# wifi.net
KiCad netlist of a schematic drawn in Altium Designer
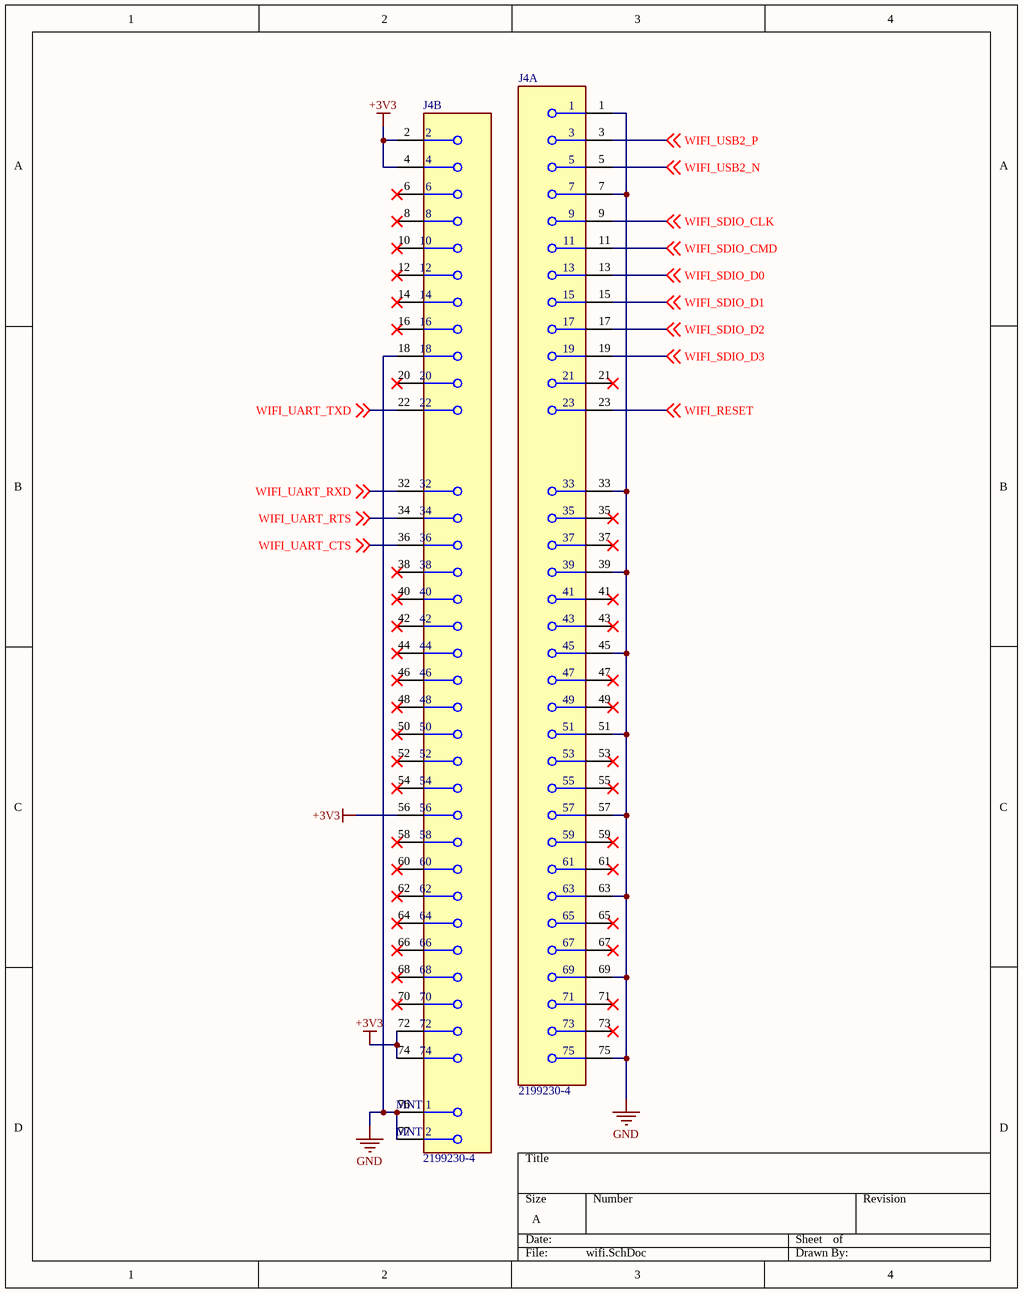
[diagram p0: wifi.SchDoc]

(export (version "E")
  (design (tool "Eeschema 10.0.6"))
  (components
    (comp (ref "J4")
      (value "2199230-4")
      (footprint "FP-2199230-4-MFG")
      (description "CONN FEMALE 67POS 0.020 GOLD")
      (fields
        (field (name "MANUFACTURER") "TE Connectivity")
        (field (name "OCTOPART") "https://octopart.com/2199230-4-te+connectivity-46436156")
      )
      (libsource (lib "Altium Content Vault") (part "6b4bc9aaecd91677fa565b830470f16"))
    )
  )
  (nets
    (net (code "1") (name "+3V3") (class "Default")
      (node (ref "J4") (pin "2") (pinfunction "2_2") (pintype "passive"))
      (node (ref "J4") (pin "4") (pinfunction "4_4") (pintype "passive"))
      (node (ref "J4") (pin "56") (pinfunction "56_56") (pintype "passive"))
      (node (ref "J4") (pin "72") (pinfunction "72_72") (pintype "passive"))
      (node (ref "J4") (pin "74") (pinfunction "74_74") (pintype "passive"))
    )
    (net (code "2") (name "GND") (class "Default")
      (node (ref "J4") (pin "1") (pinfunction "1_1") (pintype "passive"))
      (node (ref "J4") (pin "18") (pinfunction "18_18") (pintype "passive"))
      (node (ref "J4") (pin "33") (pinfunction "33_33") (pintype "passive"))
      (node (ref "J4") (pin "39") (pinfunction "39_39") (pintype "passive"))
      (node (ref "J4") (pin "45") (pinfunction "45_45") (pintype "passive"))
      (node (ref "J4") (pin "51") (pinfunction "51_51") (pintype "passive"))
      (node (ref "J4") (pin "57") (pinfunction "57_57") (pintype "passive"))
      (node (ref "J4") (pin "63") (pinfunction "63_63") (pintype "passive"))
      (node (ref "J4") (pin "69") (pinfunction "69_69") (pintype "passive"))
      (node (ref "J4") (pin "7") (pinfunction "7_7") (pintype "passive"))
      (node (ref "J4") (pin "75") (pinfunction "75_75") (pintype "passive"))
      (node (ref "J4") (pin "76") (pinfunction "MNT_1_76") (pintype "passive"))
      (node (ref "J4") (pin "77") (pinfunction "MNT_2_77") (pintype "passive"))
    )
    (net (code "3") (name "WIFI_RESET") (class "Default")
      (node (ref "J4") (pin "23") (pinfunction "23_23") (pintype "passive"))
    )
    (net (code "4") (name "WIFI_SDIO_CLK") (class "Default")
      (node (ref "J4") (pin "9") (pinfunction "9_9") (pintype "passive"))
    )
    (net (code "5") (name "WIFI_SDIO_CMD") (class "Default")
      (node (ref "J4") (pin "11") (pinfunction "11_11") (pintype "passive"))
    )
    (net (code "6") (name "WIFI_SDIO_D0") (class "Default")
      (node (ref "J4") (pin "13") (pinfunction "13_13") (pintype "passive"))
    )
    (net (code "7") (name "WIFI_SDIO_D1") (class "Default")
      (node (ref "J4") (pin "15") (pinfunction "15_15") (pintype "passive"))
    )
    (net (code "8") (name "WIFI_SDIO_D2") (class "Default")
      (node (ref "J4") (pin "17") (pinfunction "17_17") (pintype "passive"))
    )
    (net (code "9") (name "WIFI_SDIO_D3") (class "Default")
      (node (ref "J4") (pin "19") (pinfunction "19_19") (pintype "passive"))
    )
    (net (code "10") (name "WIFI_UART_CTS") (class "Default")
      (node (ref "J4") (pin "36") (pinfunction "36_36") (pintype "passive"))
    )
    (net (code "11") (name "WIFI_UART_RTS") (class "Default")
      (node (ref "J4") (pin "34") (pinfunction "34_34") (pintype "passive"))
    )
    (net (code "12") (name "WIFI_UART_RXD") (class "Default")
      (node (ref "J4") (pin "32") (pinfunction "32_32") (pintype "passive"))
    )
    (net (code "13") (name "WIFI_UART_TXD") (class "Default")
      (node (ref "J4") (pin "22") (pinfunction "22_22") (pintype "passive"))
    )
    (net (code "14") (name "WIFI_USB2_N") (class "Default")
      (node (ref "J4") (pin "5") (pinfunction "5_5") (pintype "passive"))
    )
    (net (code "15") (name "WIFI_USB2_P") (class "Default")
      (node (ref "J4") (pin "3") (pinfunction "3_3") (pintype "passive"))
    )
    (net (code "16") (name "unconnected-(J4-Pad6)") (class "Default")
      (node (ref "J4") (pin "6") (pinfunction "6_6") (pintype "passive+no_connect"))
    )
    (net (code "17") (name "unconnected-(J4-Pad8)") (class "Default")
      (node (ref "J4") (pin "8") (pinfunction "8_8") (pintype "passive+no_connect"))
    )
    (net (code "18") (name "unconnected-(J4-Pad10)") (class "Default")
      (node (ref "J4") (pin "10") (pinfunction "10_10") (pintype "passive+no_connect"))
    )
    (net (code "19") (name "unconnected-(J4-Pad12)") (class "Default")
      (node (ref "J4") (pin "12") (pinfunction "12_12") (pintype "passive+no_connect"))
    )
    (net (code "20") (name "unconnected-(J4-Pad14)") (class "Default")
      (node (ref "J4") (pin "14") (pinfunction "14_14") (pintype "passive+no_connect"))
    )
    (net (code "21") (name "unconnected-(J4-Pad16)") (class "Default")
      (node (ref "J4") (pin "16") (pinfunction "16_16") (pintype "passive+no_connect"))
    )
    (net (code "22") (name "unconnected-(J4-Pad20)") (class "Default")
      (node (ref "J4") (pin "20") (pinfunction "20_20") (pintype "passive+no_connect"))
    )
    (net (code "23") (name "unconnected-(J4-Pad21)") (class "Default")
      (node (ref "J4") (pin "21") (pinfunction "21_21") (pintype "passive+no_connect"))
    )
    (net (code "24") (name "unconnected-(J4-Pad35)") (class "Default")
      (node (ref "J4") (pin "35") (pinfunction "35_35") (pintype "passive+no_connect"))
    )
    (net (code "25") (name "unconnected-(J4-Pad37)") (class "Default")
      (node (ref "J4") (pin "37") (pinfunction "37_37") (pintype "passive+no_connect"))
    )
    (net (code "26") (name "unconnected-(J4-Pad38)") (class "Default")
      (node (ref "J4") (pin "38") (pinfunction "38_38") (pintype "passive+no_connect"))
    )
    (net (code "27") (name "unconnected-(J4-Pad40)") (class "Default")
      (node (ref "J4") (pin "40") (pinfunction "40_40") (pintype "passive+no_connect"))
    )
    (net (code "28") (name "unconnected-(J4-Pad41)") (class "Default")
      (node (ref "J4") (pin "41") (pinfunction "41_41") (pintype "passive+no_connect"))
    )
    (net (code "29") (name "unconnected-(J4-Pad42)") (class "Default")
      (node (ref "J4") (pin "42") (pinfunction "42_42") (pintype "passive+no_connect"))
    )
    (net (code "30") (name "unconnected-(J4-Pad43)") (class "Default")
      (node (ref "J4") (pin "43") (pinfunction "43_43") (pintype "passive+no_connect"))
    )
    (net (code "31") (name "unconnected-(J4-Pad44)") (class "Default")
      (node (ref "J4") (pin "44") (pinfunction "44_44") (pintype "passive+no_connect"))
    )
    (net (code "32") (name "unconnected-(J4-Pad46)") (class "Default")
      (node (ref "J4") (pin "46") (pinfunction "46_46") (pintype "passive+no_connect"))
    )
    (net (code "33") (name "unconnected-(J4-Pad47)") (class "Default")
      (node (ref "J4") (pin "47") (pinfunction "47_47") (pintype "passive+no_connect"))
    )
    (net (code "34") (name "unconnected-(J4-Pad48)") (class "Default")
      (node (ref "J4") (pin "48") (pinfunction "48_48") (pintype "passive+no_connect"))
    )
    (net (code "35") (name "unconnected-(J4-Pad49)") (class "Default")
      (node (ref "J4") (pin "49") (pinfunction "49_49") (pintype "passive+no_connect"))
    )
    (net (code "36") (name "unconnected-(J4-Pad50)") (class "Default")
      (node (ref "J4") (pin "50") (pinfunction "50_50") (pintype "passive+no_connect"))
    )
    (net (code "37") (name "unconnected-(J4-Pad52)") (class "Default")
      (node (ref "J4") (pin "52") (pinfunction "52_52") (pintype "passive+no_connect"))
    )
    (net (code "38") (name "unconnected-(J4-Pad53)") (class "Default")
      (node (ref "J4") (pin "53") (pinfunction "53_53") (pintype "passive+no_connect"))
    )
    (net (code "39") (name "unconnected-(J4-Pad54)") (class "Default")
      (node (ref "J4") (pin "54") (pinfunction "54_54") (pintype "passive+no_connect"))
    )
    (net (code "40") (name "unconnected-(J4-Pad55)") (class "Default")
      (node (ref "J4") (pin "55") (pinfunction "55_55") (pintype "passive+no_connect"))
    )
    (net (code "41") (name "unconnected-(J4-Pad58)") (class "Default")
      (node (ref "J4") (pin "58") (pinfunction "58_58") (pintype "passive+no_connect"))
    )
    (net (code "42") (name "unconnected-(J4-Pad59)") (class "Default")
      (node (ref "J4") (pin "59") (pinfunction "59_59") (pintype "passive+no_connect"))
    )
    (net (code "43") (name "unconnected-(J4-Pad60)") (class "Default")
      (node (ref "J4") (pin "60") (pinfunction "60_60") (pintype "passive+no_connect"))
    )
    (net (code "44") (name "unconnected-(J4-Pad61)") (class "Default")
      (node (ref "J4") (pin "61") (pinfunction "61_61") (pintype "passive+no_connect"))
    )
    (net (code "45") (name "unconnected-(J4-Pad62)") (class "Default")
      (node (ref "J4") (pin "62") (pinfunction "62_62") (pintype "passive+no_connect"))
    )
    (net (code "46") (name "unconnected-(J4-Pad64)") (class "Default")
      (node (ref "J4") (pin "64") (pinfunction "64_64") (pintype "passive+no_connect"))
    )
    (net (code "47") (name "unconnected-(J4-Pad65)") (class "Default")
      (node (ref "J4") (pin "65") (pinfunction "65_65") (pintype "passive+no_connect"))
    )
    (net (code "48") (name "unconnected-(J4-Pad66)") (class "Default")
      (node (ref "J4") (pin "66") (pinfunction "66_66") (pintype "passive+no_connect"))
    )
    (net (code "49") (name "unconnected-(J4-Pad67)") (class "Default")
      (node (ref "J4") (pin "67") (pinfunction "67_67") (pintype "passive+no_connect"))
    )
    (net (code "50") (name "unconnected-(J4-Pad68)") (class "Default")
      (node (ref "J4") (pin "68") (pinfunction "68_68") (pintype "passive+no_connect"))
    )
    (net (code "51") (name "unconnected-(J4-Pad70)") (class "Default")
      (node (ref "J4") (pin "70") (pinfunction "70_70") (pintype "passive+no_connect"))
    )
    (net (code "52") (name "unconnected-(J4-Pad71)") (class "Default")
      (node (ref "J4") (pin "71") (pinfunction "71_71") (pintype "passive+no_connect"))
    )
    (net (code "53") (name "unconnected-(J4-Pad73)") (class "Default")
      (node (ref "J4") (pin "73") (pinfunction "73_73") (pintype "passive+no_connect"))
    )
  )
)
